# communication.net
KiCad netlist of a schematic drawn in EAGLE
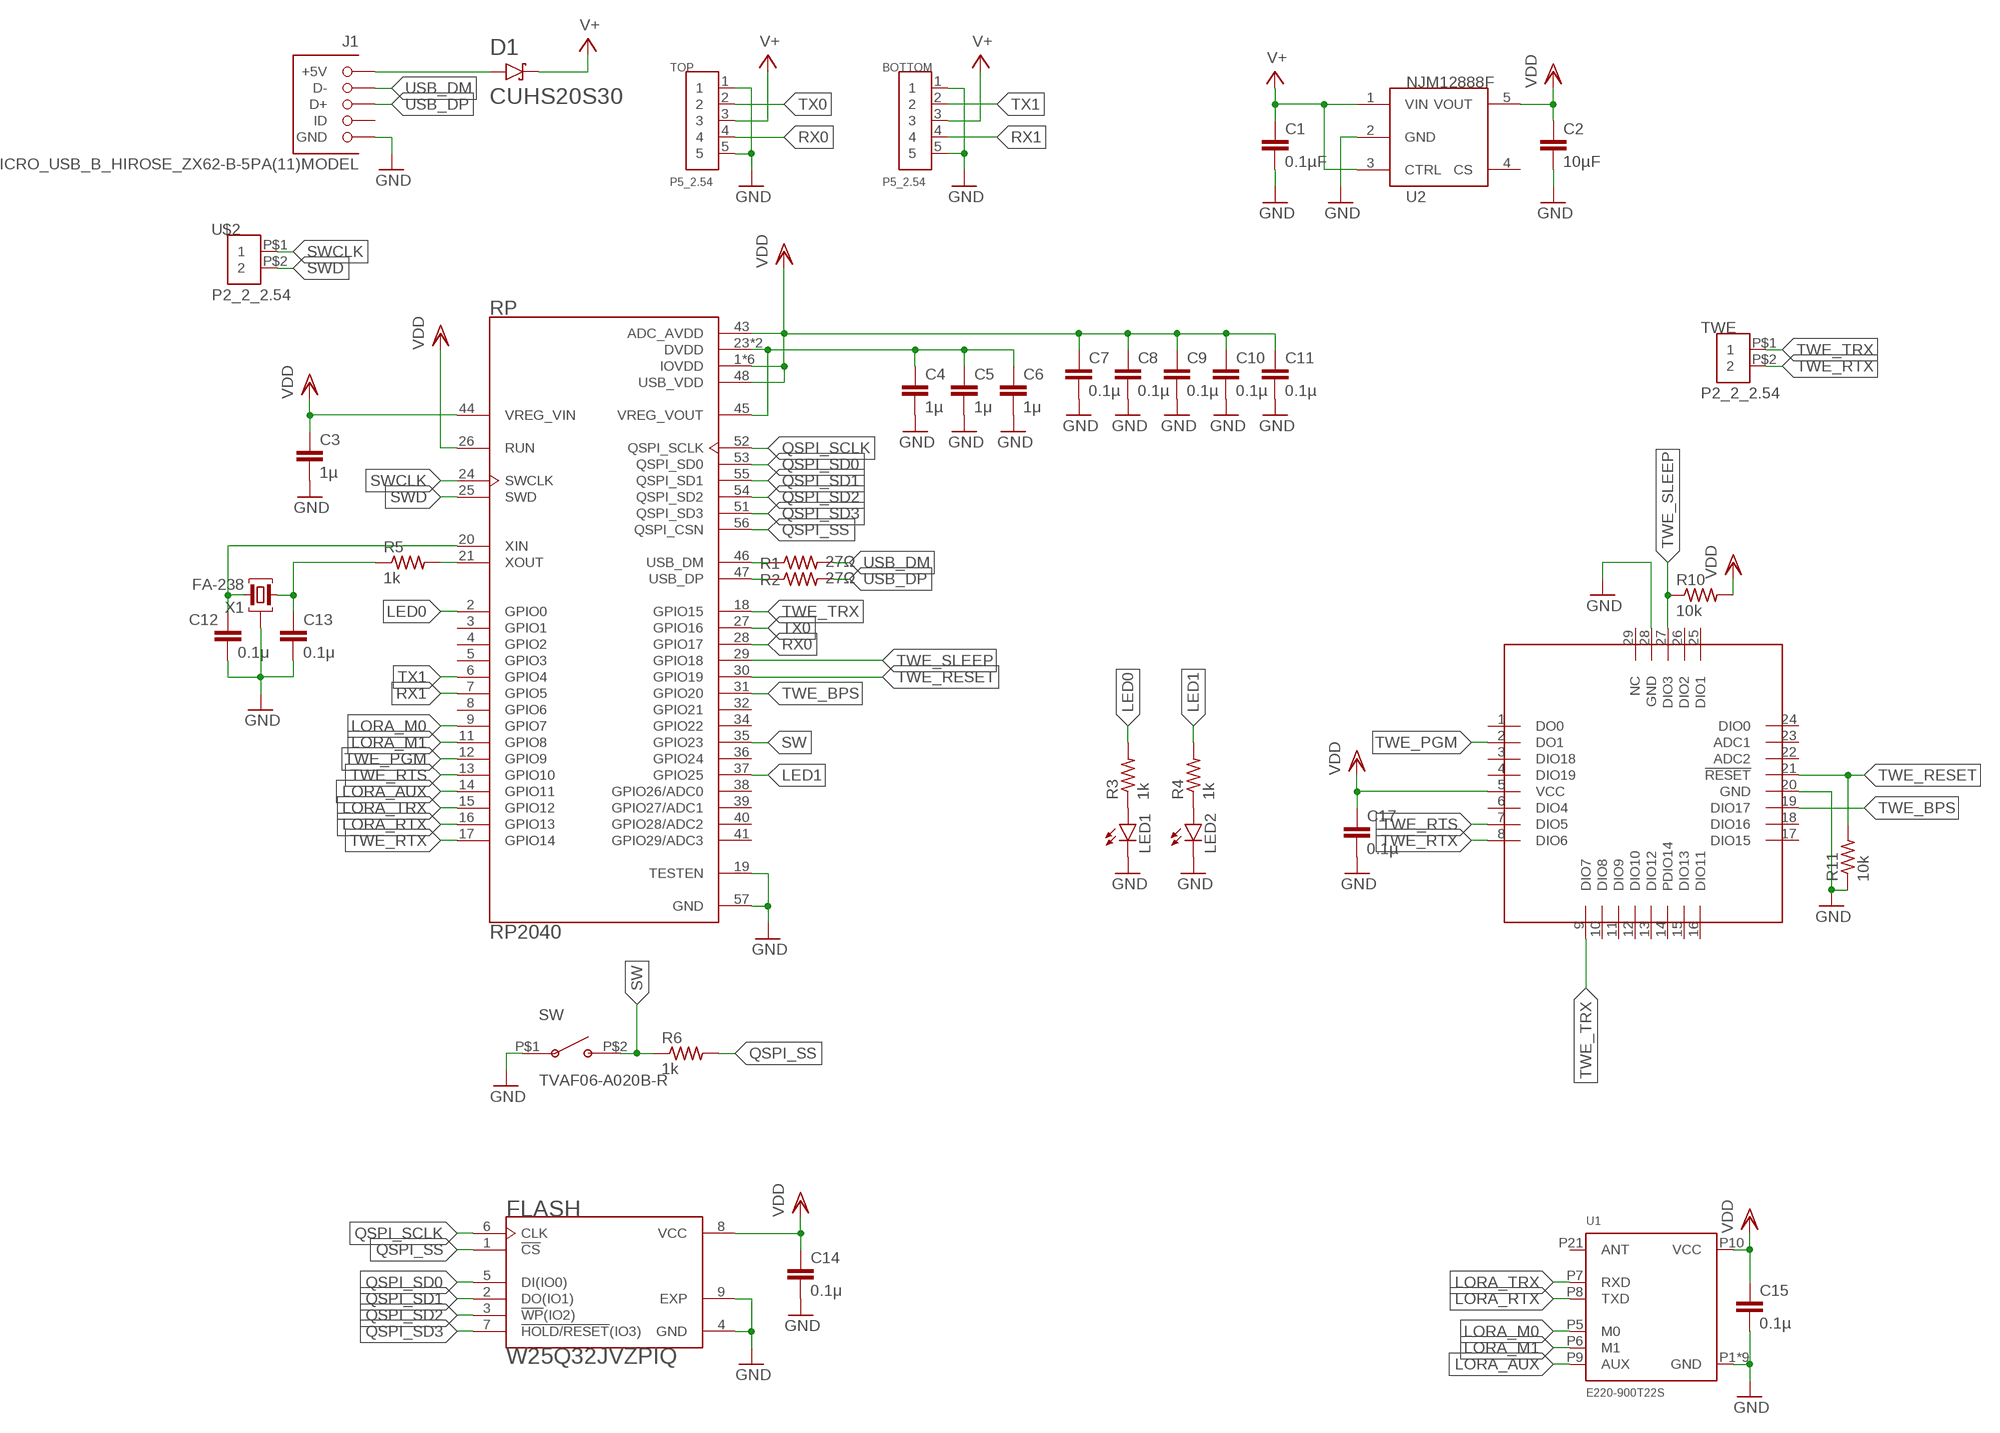
[diagram p0: schematic, sheet 1]

(export (version "E")
  (design (tool "Eeschema 10.0.6"))
  (components
    (comp (ref "BOTTOM")
      (value "P5_2.54")
      (footprint "eagle-import:P5_2.54")
      (libsource (lib "eagle-import") (part "P5_2.54"))
    )
    (comp (ref "C1")
      (value "0.1µF")
      (footprint "eagle-import:C0402")
      (libsource (lib "eagle-import") (part "C-EUC0402"))
    )
    (comp (ref "C2")
      (value "10µF")
      (footprint "eagle-import:C0402")
      (libsource (lib "eagle-import") (part "C-EUC0402"))
    )
    (comp (ref "C3")
      (value "1µ")
      (footprint "eagle-import:C0402")
      (libsource (lib "eagle-import") (part "C-EUC0402"))
    )
    (comp (ref "C4")
      (value "1µ")
      (footprint "eagle-import:C0402")
      (libsource (lib "eagle-import") (part "C-EUC0402"))
    )
    (comp (ref "C5")
      (value "1μ")
      (footprint "eagle-import:C0402")
      (libsource (lib "eagle-import") (part "C-EUC0402"))
    )
    (comp (ref "C6")
      (value "1μ")
      (footprint "eagle-import:C0402")
      (libsource (lib "eagle-import") (part "C-EUC0402"))
    )
    (comp (ref "C7")
      (value "0.1µ")
      (footprint "eagle-import:C0402")
      (libsource (lib "eagle-import") (part "C-EUC0402"))
    )
    (comp (ref "C8")
      (value "0.1µ")
      (footprint "eagle-import:C0402")
      (libsource (lib "eagle-import") (part "C-EUC0402"))
    )
    (comp (ref "C9")
      (value "0.1µ")
      (footprint "eagle-import:C0402")
      (libsource (lib "eagle-import") (part "C-EUC0402"))
    )
    (comp (ref "C10")
      (value "0.1µ")
      (footprint "eagle-import:C0402")
      (libsource (lib "eagle-import") (part "C-EUC0402"))
    )
    (comp (ref "C11")
      (value "0.1µ")
      (footprint "eagle-import:C0402")
      (libsource (lib "eagle-import") (part "C-EUC0402"))
    )
    (comp (ref "C12")
      (value "0.1μ")
      (footprint "eagle-import:C0402")
      (libsource (lib "eagle-import") (part "C-EUC0402"))
    )
    (comp (ref "C13")
      (value "0.1μ")
      (footprint "eagle-import:C0402")
      (libsource (lib "eagle-import") (part "C-EUC0402"))
    )
    (comp (ref "C14")
      (value "0.1μ")
      (footprint "eagle-import:C0402")
      (libsource (lib "eagle-import") (part "C-EUC0402"))
    )
    (comp (ref "C15")
      (value "0.1µ")
      (footprint "eagle-import:C0402")
      (libsource (lib "eagle-import") (part "C-EUC0402"))
    )
    (comp (ref "C17")
      (value "0.1µ")
      (footprint "eagle-import:C0402")
      (libsource (lib "eagle-import") (part "C-EUC0402"))
    )
    (comp (ref "D1")
      (value "CUHS20S30")
      (footprint "eagle-import:CUHS20S30")
      (libsource (lib "eagle-import") (part "CUHS20S30"))
    )
    (comp (ref "FLASH")
      (value "W25Q32JVZPIQ")
      (footprint "eagle-import:SON127P600X500X80-9N")
      (fields (field (name "MF") "Winbond"))
      (libsource (lib "eagle-import") (part "W25Q32JVZPIQ"))
    )
    (comp (ref "J1")
      (value "MICRO_USB_B_HIROSE_ZX62-B-5PA(11)MODEL")
      (footprint "eagle-import:GHI-CONNECTORS_10118192-0001LF(MICRO-USB-B-AMPHENOL-FCI)")
      (libsource (lib "eagle-import") (part "MICRO_USB_B_HIROSE_ZX62-B-5PA(11)MODEL"))
    )
    (comp (ref "LED1")
      (value "LEDCHIPLED_0603")
      (footprint "eagle-import:CHIPLED_0603")
      (libsource (lib "eagle-import") (part "LEDCHIPLED_0603"))
    )
    (comp (ref "LED2")
      (value "LEDCHIPLED_0603")
      (footprint "eagle-import:CHIPLED_0603")
      (libsource (lib "eagle-import") (part "LEDCHIPLED_0603"))
    )
    (comp (ref "R1")
      (value "27Ω")
      (footprint "eagle-import:R0402")
      (libsource (lib "eagle-import") (part "R-US_R0402"))
    )
    (comp (ref "R2")
      (value "27Ω")
      (footprint "eagle-import:R0402")
      (libsource (lib "eagle-import") (part "R-US_R0402"))
    )
    (comp (ref "R3")
      (value "1k")
      (footprint "eagle-import:R0402")
      (libsource (lib "eagle-import") (part "R-US_R0402"))
    )
    (comp (ref "R4")
      (value "1k")
      (footprint "eagle-import:R0402")
      (libsource (lib "eagle-import") (part "R-US_R0402"))
    )
    (comp (ref "R5")
      (value "1k")
      (footprint "eagle-import:R0402")
      (libsource (lib "eagle-import") (part "R-US_R0402"))
    )
    (comp (ref "R6")
      (value "1k")
      (footprint "eagle-import:R0402")
      (libsource (lib "eagle-import") (part "R-US_R0402"))
    )
    (comp (ref "R10")
      (value "10k")
      (footprint "eagle-import:R0402")
      (libsource (lib "eagle-import") (part "R-US_R0402"))
    )
    (comp (ref "R11")
      (value "10k")
      (footprint "eagle-import:R0402")
      (libsource (lib "eagle-import") (part "R-US_R0402"))
    )
    (comp (ref "RP")
      (value "RP2040")
      (footprint "eagle-import:QFN40P700X700X90-57N")
      (fields (field (name "MF") "Raspberry Pi"))
      (libsource (lib "eagle-import") (part "RP2040"))
    )
    (comp (ref "SW")
      (value "TVAF06-A020B-R")
      (footprint "eagle-import:TVAF06-A020B-R")
      (libsource (lib "eagle-import") (part "TVAF06-A020B-R"))
    )
    (comp (ref "TOP")
      (value "P5_2.54")
      (footprint "eagle-import:P5_2.54")
      (libsource (lib "eagle-import") (part "P5_2.54"))
    )
    (comp (ref "TWE")
      (value "P2_2_2.54")
      (footprint "eagle-import:P2_2.54")
      (libsource (lib "eagle-import") (part "P2_2_2.54"))
    )
    (comp (ref "U$1")
      (value "LITE")
      (footprint "eagle-import:LITE")
      (libsource (lib "eagle-import") (part "LITE"))
    )
    (comp (ref "U$2")
      (value "P2_2_2.54")
      (footprint "eagle-import:P2_2.54")
      (libsource (lib "eagle-import") (part "P2_2_2.54"))
    )
    (comp (ref "U1")
      (value "E220-900T22S")
      (footprint "eagle-import:E220-900T22S")
      (libsource (lib "eagle-import") (part "E220-900T22S"))
    )
    (comp (ref "U2")
      (value "NJM12888F")
      (footprint "eagle-import:SOT95P240X110-5N")
      (libsource (lib "eagle-import") (part "NJM12888F"))
    )
    (comp (ref "X1")
      (value "FA-238")
      (footprint "eagle-import:FA-238")
      (libsource (lib "eagle-import") (part "FA-238"))
    )
  )
  (nets
    (net (code "1") (name "GND") (class "Default")
      (node (ref "BOTTOM") (pin "1") (pinfunction "1_1") (pintype "bidirectional"))
      (node (ref "BOTTOM") (pin "5") (pinfunction "5_5") (pintype "bidirectional"))
      (node (ref "C1") (pin "2") (pinfunction "2_2") (pintype "passive"))
      (node (ref "C10") (pin "2") (pinfunction "2_2") (pintype "passive"))
      (node (ref "C11") (pin "2") (pinfunction "2_2") (pintype "passive"))
      (node (ref "C12") (pin "2") (pinfunction "2_2") (pintype "passive"))
      (node (ref "C13") (pin "2") (pinfunction "2_2") (pintype "passive"))
      (node (ref "C14") (pin "2") (pinfunction "2_2") (pintype "passive"))
      (node (ref "C15") (pin "2") (pinfunction "2_2") (pintype "passive"))
      (node (ref "C17") (pin "2") (pinfunction "2_2") (pintype "passive"))
      (node (ref "C2") (pin "2") (pinfunction "2_2") (pintype "passive"))
      (node (ref "C3") (pin "2") (pinfunction "2_2") (pintype "passive"))
      (node (ref "C4") (pin "2") (pinfunction "2_2") (pintype "passive"))
      (node (ref "C5") (pin "2") (pinfunction "2_2") (pintype "passive"))
      (node (ref "C6") (pin "2") (pinfunction "2_2") (pintype "passive"))
      (node (ref "C7") (pin "2") (pinfunction "2_2") (pintype "passive"))
      (node (ref "C8") (pin "2") (pinfunction "2_2") (pintype "passive"))
      (node (ref "C9") (pin "2") (pinfunction "2_2") (pintype "passive"))
      (node (ref "FLASH") (pin "4") (pinfunction "GND_4") (pintype "power_in"))
      (node (ref "FLASH") (pin "9") (pinfunction "EXP_9") (pintype "passive"))
      (node (ref "J1") (pin "CGND1") (pinfunction "GND_CGND1") (pintype "bidirectional"))
      (node (ref "J1") (pin "CGND2") (pinfunction "GND_CGND2") (pintype "bidirectional"))
      (node (ref "J1") (pin "CGND3") (pinfunction "GND_CGND3") (pintype "bidirectional"))
      (node (ref "J1") (pin "CGND4") (pinfunction "GND_CGND4") (pintype "bidirectional"))
      (node (ref "J1") (pin "CGND5") (pinfunction "GND_CGND5") (pintype "bidirectional"))
      (node (ref "J1") (pin "CGND6") (pinfunction "GND_CGND6") (pintype "bidirectional"))
      (node (ref "J1") (pin "GND") (pinfunction "GND_GND") (pintype "bidirectional"))
      (node (ref "LED1") (pin "C") (pinfunction "C_C") (pintype "passive"))
      (node (ref "LED2") (pin "C") (pinfunction "C_C") (pintype "passive"))
      (node (ref "R11") (pin "1") (pinfunction "1_1") (pintype "passive"))
      (node (ref "RP") (pin "19") (pinfunction "TESTEN_19") (pintype "passive"))
      (node (ref "RP") (pin "57") (pinfunction "GND_57") (pintype "power_in"))
      (node (ref "SW") (pin "P$1") (pinfunction "A_P$1") (pintype "bidirectional"))
      (node (ref "TOP") (pin "1") (pinfunction "1_1") (pintype "bidirectional"))
      (node (ref "TOP") (pin "5") (pinfunction "5_5") (pintype "bidirectional"))
      (node (ref "U$1") (pin "20") (pinfunction "GND_20") (pintype "power_in"))
      (node (ref "U$1") (pin "28") (pinfunction "GND_28") (pintype "power_in"))
      (node (ref "U1") (pin "P1") (pinfunction "GND_P1") (pintype "bidirectional"))
      (node (ref "U1") (pin "P11") (pinfunction "GND_P11") (pintype "bidirectional"))
      (node (ref "U1") (pin "P13") (pinfunction "GND_P13") (pintype "bidirectional"))
      (node (ref "U1") (pin "P19") (pinfunction "GND_P19") (pintype "bidirectional"))
      (node (ref "U1") (pin "P2") (pinfunction "GND_P2") (pintype "bidirectional"))
      (node (ref "U1") (pin "P20") (pinfunction "GND_P20") (pintype "bidirectional"))
      (node (ref "U1") (pin "P22") (pinfunction "GND_P22") (pintype "bidirectional"))
      (node (ref "U1") (pin "P3") (pinfunction "GND_P3") (pintype "bidirectional"))
      (node (ref "U1") (pin "P4") (pinfunction "GND_P4") (pintype "bidirectional"))
      (node (ref "U2") (pin "2") (pinfunction "GND_2") (pintype "power_in"))
      (node (ref "X1") (pin "2") (pinfunction "G_2") (pintype "passive"))
      (node (ref "X1") (pin "4") (pinfunction "G_4") (pintype "passive"))
    )
    (net (code "2") (name "LED0") (class "Default")
      (node (ref "R3") (pin "2") (pinfunction "2_2") (pintype "passive"))
      (node (ref "RP") (pin "2") (pinfunction "GPIO0_2") (pintype "bidirectional"))
    )
    (net (code "3") (name "LED1") (class "Default")
      (node (ref "R4") (pin "2") (pinfunction "2_2") (pintype "passive"))
      (node (ref "RP") (pin "37") (pinfunction "GPIO25_37") (pintype "bidirectional"))
    )
    (net (code "4") (name "LORA_AUX") (class "Default")
      (node (ref "RP") (pin "14") (pinfunction "GPIO11_14") (pintype "bidirectional"))
      (node (ref "U1") (pin "P9") (pinfunction "AUX_P9") (pintype "bidirectional"))
    )
    (net (code "5") (name "LORA_M0") (class "Default")
      (node (ref "RP") (pin "9") (pinfunction "GPIO7_9") (pintype "bidirectional"))
      (node (ref "U1") (pin "P5") (pinfunction "M0_P5") (pintype "bidirectional"))
    )
    (net (code "6") (name "LORA_M1") (class "Default")
      (node (ref "RP") (pin "11") (pinfunction "GPIO8_11") (pintype "bidirectional"))
      (node (ref "U1") (pin "P6") (pinfunction "M1_P6") (pintype "bidirectional"))
    )
    (net (code "7") (name "LORA_RTX") (class "Default")
      (node (ref "RP") (pin "16") (pinfunction "GPIO13_16") (pintype "bidirectional"))
      (node (ref "U1") (pin "P8") (pinfunction "TXD_P8") (pintype "bidirectional"))
    )
    (net (code "8") (name "LORA_TRX") (class "Default")
      (node (ref "RP") (pin "15") (pinfunction "GPIO12_15") (pintype "bidirectional"))
      (node (ref "U1") (pin "P7") (pinfunction "RXD_P7") (pintype "bidirectional"))
    )
    (net (code "9") (name "Net-(C13-Pad1)") (class "Default")
      (node (ref "C13") (pin "1") (pinfunction "1_1") (pintype "passive"))
      (node (ref "R5") (pin "1") (pinfunction "1_1") (pintype "passive"))
      (node (ref "X1") (pin "1") (pinfunction "1_1") (pintype "passive"))
    )
    (net (code "10") (name "Net-(J1-+5V)") (class "Default")
      (node (ref "D1") (pin "A") (pinfunction "A_A") (pintype "bidirectional"))
      (node (ref "J1") (pin "VBUS") (pinfunction "+5V_VBUS") (pintype "bidirectional"))
    )
    (net (code "11") (name "Net-(LED1-PadA)") (class "Default")
      (node (ref "LED1") (pin "A") (pinfunction "A_A") (pintype "passive"))
      (node (ref "R3") (pin "1") (pinfunction "1_1") (pintype "passive"))
    )
    (net (code "12") (name "Net-(LED2-PadA)") (class "Default")
      (node (ref "LED2") (pin "A") (pinfunction "A_A") (pintype "passive"))
      (node (ref "R4") (pin "1") (pinfunction "1_1") (pintype "passive"))
    )
    (net (code "13") (name "Net-(RP-USB_DM)") (class "Default")
      (node (ref "R1") (pin "1") (pinfunction "1_1") (pintype "passive"))
      (node (ref "RP") (pin "46") (pinfunction "USB_DM_46") (pintype "bidirectional"))
    )
    (net (code "14") (name "Net-(RP-USB_DP)") (class "Default")
      (node (ref "R2") (pin "1") (pinfunction "1_1") (pintype "passive"))
      (node (ref "RP") (pin "47") (pinfunction "USB_DP_47") (pintype "bidirectional"))
    )
    (net (code "15") (name "Net-(RP-VREG_VOUT)") (class "Default")
      (node (ref "C4") (pin "1") (pinfunction "1_1") (pintype "passive"))
      (node (ref "C5") (pin "1") (pinfunction "1_1") (pintype "passive"))
      (node (ref "C6") (pin "1") (pinfunction "1_1") (pintype "passive"))
      (node (ref "RP") (pin "23") (pinfunction "DVDD_23") (pintype "power_in"))
      (node (ref "RP") (pin "45") (pinfunction "VREG_VOUT_45") (pintype "output"))
      (node (ref "RP") (pin "50") (pinfunction "DVDD_50") (pintype "power_in"))
    )
    (net (code "16") (name "Net-(RP-XIN)") (class "Default")
      (node (ref "C12") (pin "1") (pinfunction "1_1") (pintype "passive"))
      (node (ref "RP") (pin "20") (pinfunction "XIN_20") (pintype "input"))
      (node (ref "X1") (pin "3") (pinfunction "2_3") (pintype "passive"))
    )
    (net (code "17") (name "Net-(RP-XOUT)") (class "Default")
      (node (ref "R5") (pin "2") (pinfunction "2_2") (pintype "passive"))
      (node (ref "RP") (pin "21") (pinfunction "XOUT_21") (pintype "output"))
    )
    (net (code "18") (name "QSPI_SCLK") (class "Default")
      (node (ref "FLASH") (pin "6") (pinfunction "CLK_6") (pintype "input"))
      (node (ref "RP") (pin "52") (pinfunction "QSPI_SCLK_52") (pintype "bidirectional"))
    )
    (net (code "19") (name "QSPI_SD0") (class "Default")
      (node (ref "FLASH") (pin "5") (pinfunction "DI(IO0)_5") (pintype "bidirectional"))
      (node (ref "RP") (pin "53") (pinfunction "QSPI_SD0_53") (pintype "bidirectional"))
    )
    (net (code "20") (name "QSPI_SD1") (class "Default")
      (node (ref "FLASH") (pin "2") (pinfunction "DO(IO1)_2") (pintype "bidirectional"))
      (node (ref "RP") (pin "55") (pinfunction "QSPI_SD1_55") (pintype "bidirectional"))
    )
    (net (code "21") (name "QSPI_SD2") (class "Default")
      (node (ref "FLASH") (pin "3") (pinfunction "~{WP}(IO2)_3") (pintype "bidirectional"))
      (node (ref "RP") (pin "54") (pinfunction "QSPI_SD2_54") (pintype "bidirectional"))
    )
    (net (code "22") (name "QSPI_SD3") (class "Default")
      (node (ref "FLASH") (pin "7") (pinfunction "~{HOLD/RESET}(IO3)_7") (pintype "bidirectional"))
      (node (ref "RP") (pin "51") (pinfunction "QSPI_SD3_51") (pintype "bidirectional"))
    )
    (net (code "23") (name "QSPI_SS") (class "Default")
      (node (ref "FLASH") (pin "1") (pinfunction "~{CS}_1") (pintype "input"))
      (node (ref "R6") (pin "2") (pinfunction "2_2") (pintype "passive"))
      (node (ref "RP") (pin "56") (pinfunction "QSPI_CSN_56") (pintype "bidirectional"))
    )
    (net (code "24") (name "RX0") (class "Default")
      (node (ref "RP") (pin "28") (pinfunction "GPIO17_28") (pintype "bidirectional"))
      (node (ref "TOP") (pin "4") (pinfunction "4_4") (pintype "bidirectional"))
    )
    (net (code "25") (name "RX1") (class "Default")
      (node (ref "BOTTOM") (pin "4") (pinfunction "4_4") (pintype "bidirectional"))
      (node (ref "RP") (pin "7") (pinfunction "GPIO5_7") (pintype "bidirectional"))
    )
    (net (code "26") (name "SW") (class "Default")
      (node (ref "R6") (pin "1") (pinfunction "1_1") (pintype "passive"))
      (node (ref "RP") (pin "35") (pinfunction "GPIO23_35") (pintype "bidirectional"))
      (node (ref "SW") (pin "P$2") (pinfunction "B_P$2") (pintype "bidirectional"))
    )
    (net (code "27") (name "SWCLK") (class "Default")
      (node (ref "RP") (pin "24") (pinfunction "SWCLK_24") (pintype "input"))
      (node (ref "U$2") (pin "P$1") (pinfunction "1_P$1") (pintype "bidirectional"))
    )
    (net (code "28") (name "SWD") (class "Default")
      (node (ref "RP") (pin "25") (pinfunction "SWD_25") (pintype "bidirectional"))
      (node (ref "U$2") (pin "P$2") (pinfunction "2_P$2") (pintype "bidirectional"))
    )
    (net (code "29") (name "TWE_BPS") (class "Default")
      (node (ref "RP") (pin "31") (pinfunction "GPIO20_31") (pintype "bidirectional"))
      (node (ref "U$1") (pin "19") (pinfunction "DIO17_19") (pintype "bidirectional"))
    )
    (net (code "30") (name "TWE_PGM") (class "Default")
      (node (ref "RP") (pin "12") (pinfunction "GPIO9_12") (pintype "bidirectional"))
      (node (ref "U$1") (pin "2") (pinfunction "DO1_2") (pintype "bidirectional"))
    )
    (net (code "31") (name "TWE_RESET") (class "Default")
      (node (ref "R11") (pin "2") (pinfunction "2_2") (pintype "passive"))
      (node (ref "RP") (pin "30") (pinfunction "GPIO19_30") (pintype "bidirectional"))
      (node (ref "U$1") (pin "21") (pinfunction "~{RESET}_21") (pintype "input"))
    )
    (net (code "32") (name "TWE_RTS") (class "Default")
      (node (ref "RP") (pin "13") (pinfunction "GPIO10_13") (pintype "bidirectional"))
      (node (ref "U$1") (pin "7") (pinfunction "DIO5_7") (pintype "bidirectional"))
    )
    (net (code "33") (name "TWE_RTX") (class "Default")
      (node (ref "RP") (pin "17") (pinfunction "GPIO14_17") (pintype "bidirectional"))
      (node (ref "TWE") (pin "P$2") (pinfunction "2_P$2") (pintype "bidirectional"))
      (node (ref "U$1") (pin "8") (pinfunction "DIO6_8") (pintype "bidirectional"))
    )
    (net (code "34") (name "TWE_SLEEP") (class "Default")
      (node (ref "R10") (pin "1") (pinfunction "1_1") (pintype "passive"))
      (node (ref "RP") (pin "29") (pinfunction "GPIO18_29") (pintype "bidirectional"))
      (node (ref "U$1") (pin "27") (pinfunction "DIO3_27") (pintype "bidirectional"))
    )
    (net (code "35") (name "TWE_TRX") (class "Default")
      (node (ref "RP") (pin "18") (pinfunction "GPIO15_18") (pintype "bidirectional"))
      (node (ref "TWE") (pin "P$1") (pinfunction "1_P$1") (pintype "bidirectional"))
      (node (ref "U$1") (pin "9") (pinfunction "DIO7_9") (pintype "bidirectional"))
    )
    (net (code "36") (name "TX0") (class "Default")
      (node (ref "RP") (pin "27") (pinfunction "GPIO16_27") (pintype "bidirectional"))
      (node (ref "TOP") (pin "2") (pinfunction "2_2") (pintype "bidirectional"))
    )
    (net (code "37") (name "TX1") (class "Default")
      (node (ref "BOTTOM") (pin "2") (pinfunction "2_2") (pintype "bidirectional"))
      (node (ref "RP") (pin "6") (pinfunction "GPIO4_6") (pintype "bidirectional"))
    )
    (net (code "38") (name "USB_DM") (class "Default")
      (node (ref "J1") (pin "D-") (pinfunction "D-_D-") (pintype "bidirectional"))
      (node (ref "R1") (pin "2") (pinfunction "2_2") (pintype "passive"))
    )
    (net (code "39") (name "USB_DP") (class "Default")
      (node (ref "J1") (pin "D+") (pinfunction "D+_D+") (pintype "bidirectional"))
      (node (ref "R2") (pin "2") (pinfunction "2_2") (pintype "passive"))
    )
    (net (code "40") (name "V+") (class "Default")
      (node (ref "BOTTOM") (pin "3") (pinfunction "3_3") (pintype "bidirectional"))
      (node (ref "C1") (pin "1") (pinfunction "1_1") (pintype "passive"))
      (node (ref "D1") (pin "C") (pinfunction "C_C") (pintype "bidirectional"))
      (node (ref "TOP") (pin "3") (pinfunction "3_3") (pintype "bidirectional"))
      (node (ref "U2") (pin "1") (pinfunction "VIN_1") (pintype "power_in"))
      (node (ref "U2") (pin "3") (pinfunction "CTRL_3") (pintype "input"))
    )
    (net (code "41") (name "VDD") (class "Default")
      (node (ref "C10") (pin "1") (pinfunction "1_1") (pintype "passive"))
      (node (ref "C11") (pin "1") (pinfunction "1_1") (pintype "passive"))
      (node (ref "C14") (pin "1") (pinfunction "1_1") (pintype "passive"))
      (node (ref "C15") (pin "1") (pinfunction "1_1") (pintype "passive"))
      (node (ref "C17") (pin "1") (pinfunction "1_1") (pintype "passive"))
      (node (ref "C2") (pin "1") (pinfunction "1_1") (pintype "passive"))
      (node (ref "C3") (pin "1") (pinfunction "1_1") (pintype "passive"))
      (node (ref "C7") (pin "1") (pinfunction "1_1") (pintype "passive"))
      (node (ref "C8") (pin "1") (pinfunction "1_1") (pintype "passive"))
      (node (ref "C9") (pin "1") (pinfunction "1_1") (pintype "passive"))
      (node (ref "FLASH") (pin "8") (pinfunction "VCC_8") (pintype "power_in"))
      (node (ref "R10") (pin "2") (pinfunction "2_2") (pintype "passive"))
      (node (ref "RP") (pin "1") (pinfunction "IOVDD_1") (pintype "power_in"))
      (node (ref "RP") (pin "10") (pinfunction "IOVDD_10") (pintype "power_in"))
      (node (ref "RP") (pin "22") (pinfunction "IOVDD_22") (pintype "power_in"))
      (node (ref "RP") (pin "26") (pinfunction "RUN_26") (pintype "input"))
      (node (ref "RP") (pin "33") (pinfunction "IOVDD_33") (pintype "power_in"))
      (node (ref "RP") (pin "42") (pinfunction "IOVDD_42") (pintype "power_in"))
      (node (ref "RP") (pin "43") (pinfunction "ADC_AVDD_43") (pintype "power_in"))
      (node (ref "RP") (pin "44") (pinfunction "VREG_VIN_44") (pintype "input"))
      (node (ref "RP") (pin "48") (pinfunction "USB_VDD_48") (pintype "power_in"))
      (node (ref "RP") (pin "49") (pinfunction "IOVDD_49") (pintype "power_in"))
      (node (ref "U$1") (pin "5") (pinfunction "VCC_5") (pintype "power_in"))
      (node (ref "U1") (pin "P10") (pinfunction "VCC_P10") (pintype "bidirectional"))
      (node (ref "U2") (pin "5") (pinfunction "VOUT_5") (pintype "power_in"))
    )
    (net (code "42") (name "unconnected-(J1-PadID)") (class "Default")
      (node (ref "J1") (pin "ID") (pinfunction "ID_ID") (pintype "bidirectional"))
    )
    (net (code "43") (name "unconnected-(RP-GPIO1-Pad3)") (class "Default")
      (node (ref "RP") (pin "3") (pinfunction "GPIO1_3") (pintype "bidirectional"))
    )
    (net (code "44") (name "unconnected-(RP-GPIO2-Pad4)") (class "Default")
      (node (ref "RP") (pin "4") (pinfunction "GPIO2_4") (pintype "bidirectional"))
    )
    (net (code "45") (name "unconnected-(RP-GPIO3-Pad5)") (class "Default")
      (node (ref "RP") (pin "5") (pinfunction "GPIO3_5") (pintype "bidirectional"))
    )
    (net (code "46") (name "unconnected-(RP-GPIO6-Pad8)") (class "Default")
      (node (ref "RP") (pin "8") (pinfunction "GPIO6_8") (pintype "bidirectional"))
    )
    (net (code "47") (name "unconnected-(RP-GPIO21-Pad32)") (class "Default")
      (node (ref "RP") (pin "32") (pinfunction "GPIO21_32") (pintype "bidirectional"))
    )
    (net (code "48") (name "unconnected-(RP-GPIO22-Pad34)") (class "Default")
      (node (ref "RP") (pin "34") (pinfunction "GPIO22_34") (pintype "bidirectional"))
    )
    (net (code "49") (name "unconnected-(RP-GPIO24-Pad36)") (class "Default")
      (node (ref "RP") (pin "36") (pinfunction "GPIO24_36") (pintype "bidirectional"))
    )
    (net (code "50") (name "unconnected-(RP-GPIO26{slash}ADC0-Pad38)") (class "Default")
      (node (ref "RP") (pin "38") (pinfunction "GPIO26/ADC0_38") (pintype "bidirectional"))
    )
    (net (code "51") (name "unconnected-(RP-GPIO27{slash}ADC1-Pad39)") (class "Default")
      (node (ref "RP") (pin "39") (pinfunction "GPIO27/ADC1_39") (pintype "bidirectional"))
    )
    (net (code "52") (name "unconnected-(RP-GPIO28{slash}ADC2-Pad40)") (class "Default")
      (node (ref "RP") (pin "40") (pinfunction "GPIO28/ADC2_40") (pintype "bidirectional"))
    )
    (net (code "53") (name "unconnected-(RP-GPIO29{slash}ADC3-Pad41)") (class "Default")
      (node (ref "RP") (pin "41") (pinfunction "GPIO29/ADC3_41") (pintype "bidirectional"))
    )
    (net (code "54") (name "unconnected-(U$1-ADC1-Pad23)") (class "Default")
      (node (ref "U$1") (pin "23") (pinfunction "ADC1_23") (pintype "bidirectional"))
    )
    (net (code "55") (name "unconnected-(U$1-ADC2-Pad22)") (class "Default")
      (node (ref "U$1") (pin "22") (pinfunction "ADC2_22") (pintype "bidirectional"))
    )
    (net (code "56") (name "unconnected-(U$1-DIO0-Pad24)") (class "Default")
      (node (ref "U$1") (pin "24") (pinfunction "DIO0_24") (pintype "bidirectional"))
    )
    (net (code "57") (name "unconnected-(U$1-DIO1-Pad25)") (class "Default")
      (node (ref "U$1") (pin "25") (pinfunction "DIO1_25") (pintype "bidirectional"))
    )
    (net (code "58") (name "unconnected-(U$1-DIO2-Pad26)") (class "Default")
      (node (ref "U$1") (pin "26") (pinfunction "DIO2_26") (pintype "bidirectional"))
    )
    (net (code "59") (name "unconnected-(U$1-DIO4-Pad6)") (class "Default")
      (node (ref "U$1") (pin "6") (pinfunction "DIO4_6") (pintype "bidirectional"))
    )
    (net (code "60") (name "unconnected-(U$1-DIO8-Pad10)") (class "Default")
      (node (ref "U$1") (pin "10") (pinfunction "DIO8_10") (pintype "bidirectional"))
    )
    (net (code "61") (name "unconnected-(U$1-DIO9-Pad11)") (class "Default")
      (node (ref "U$1") (pin "11") (pinfunction "DIO9_11") (pintype "bidirectional"))
    )
    (net (code "62") (name "unconnected-(U$1-DIO10-Pad12)") (class "Default")
      (node (ref "U$1") (pin "12") (pinfunction "DIO10_12") (pintype "bidirectional"))
    )
    (net (code "63") (name "unconnected-(U$1-DIO11-Pad16)") (class "Default")
      (node (ref "U$1") (pin "16") (pinfunction "DIO11_16") (pintype "bidirectional"))
    )
    (net (code "64") (name "unconnected-(U$1-DIO12-Pad13)") (class "Default")
      (node (ref "U$1") (pin "13") (pinfunction "DIO12_13") (pintype "bidirectional"))
    )
    (net (code "65") (name "unconnected-(U$1-DIO13-Pad15)") (class "Default")
      (node (ref "U$1") (pin "15") (pinfunction "DIO13_15") (pintype "bidirectional"))
    )
    (net (code "66") (name "unconnected-(U$1-DIO15-Pad17)") (class "Default")
      (node (ref "U$1") (pin "17") (pinfunction "DIO15_17") (pintype "bidirectional"))
    )
    (net (code "67") (name "unconnected-(U$1-DIO16-Pad18)") (class "Default")
      (node (ref "U$1") (pin "18") (pinfunction "DIO16_18") (pintype "bidirectional"))
    )
    (net (code "68") (name "unconnected-(U$1-DIO18-Pad3)") (class "Default")
      (node (ref "U$1") (pin "3") (pinfunction "DIO18_3") (pintype "bidirectional"))
    )
    (net (code "69") (name "unconnected-(U$1-DIO19-Pad4)") (class "Default")
      (node (ref "U$1") (pin "4") (pinfunction "DIO19_4") (pintype "bidirectional"))
    )
    (net (code "70") (name "unconnected-(U$1-DO0-Pad1)") (class "Default")
      (node (ref "U$1") (pin "1") (pinfunction "DO0_1") (pintype "output"))
    )
    (net (code "71") (name "unconnected-(U$1-NC-Pad29)") (class "Default")
      (node (ref "U$1") (pin "29") (pinfunction "NC_29") (pintype "no_connect"))
    )
    (net (code "72") (name "unconnected-(U$1-PDIO14-Pad14)") (class "Default")
      (node (ref "U$1") (pin "14") (pinfunction "PDIO14_14") (pintype "bidirectional"))
    )
    (net (code "73") (name "unconnected-(U1-ANT-PadP21)") (class "Default")
      (node (ref "U1") (pin "P21") (pinfunction "ANT_P21") (pintype "bidirectional"))
    )
    (net (code "74") (name "unconnected-(U2-CS-Pad4)") (class "Default")
      (node (ref "U2") (pin "4") (pinfunction "CS_4") (pintype "input"))
    )
  )
)
